# LevelConverter.net
KiCad netlist of a schematic drawn in Altium Designer
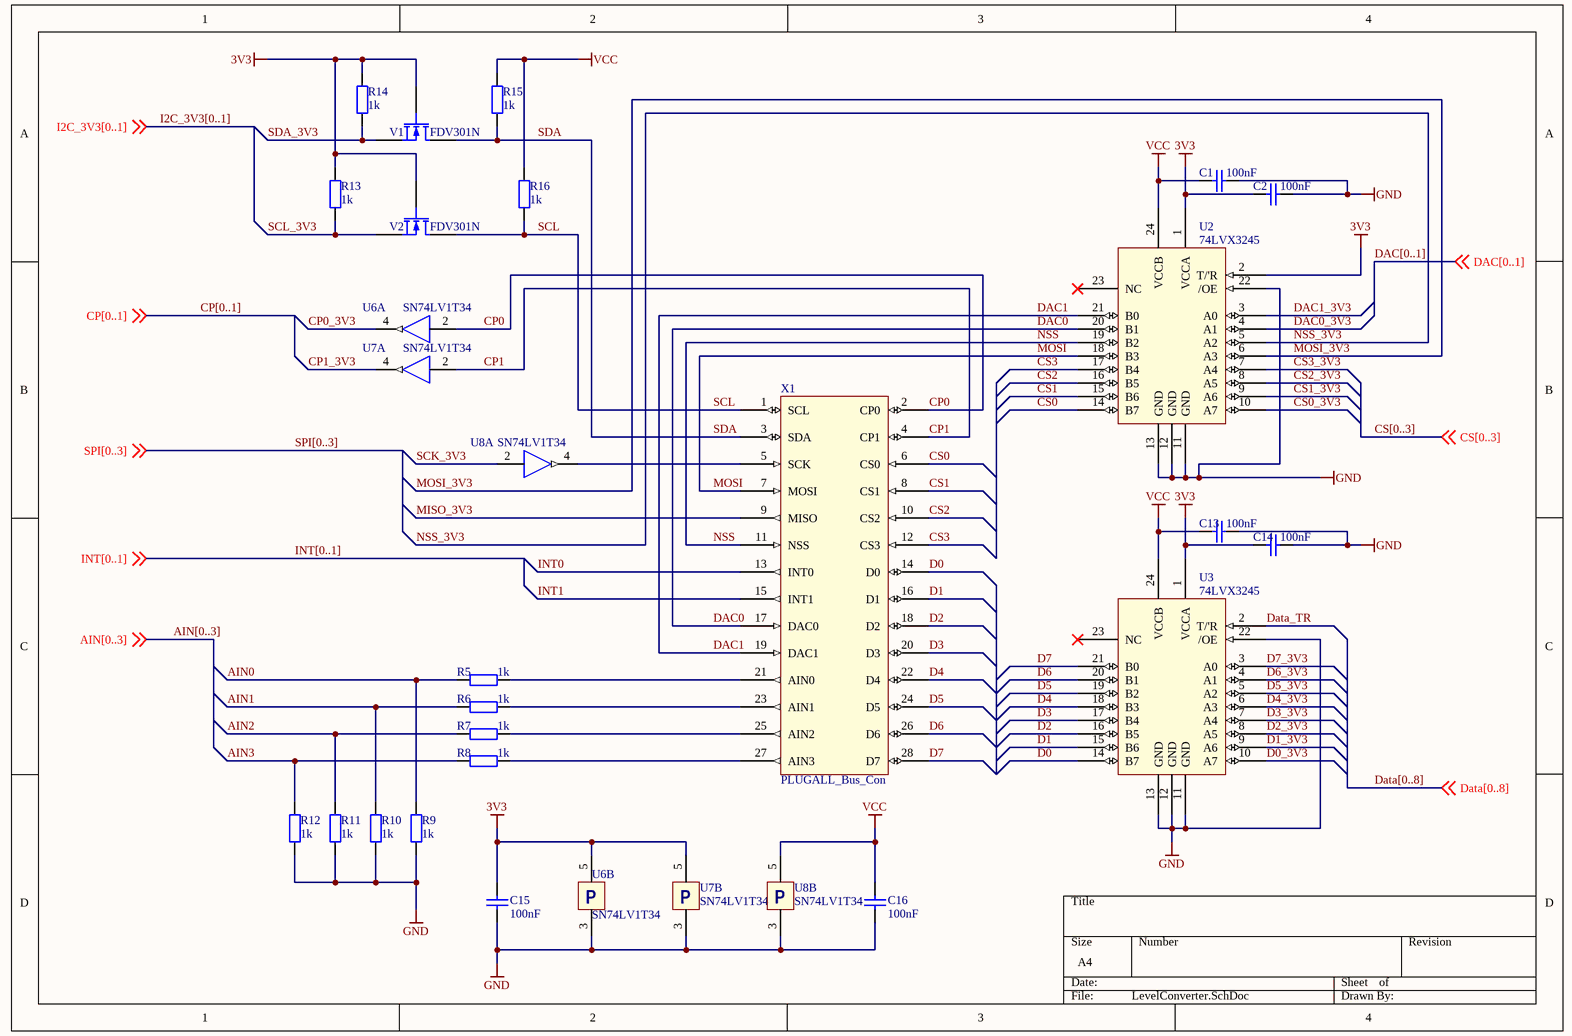
[diagram p0: LevelConverter.SchDoc]

(export (version "E")
  (design (tool "Eeschema 10.0.6"))
  (components
    (comp (ref "C1")
      (value "100nF")
      (footprint "0805")
      (fields (field (name "Comment") "C"))
      (libsource (lib "Schlib1") (part "C"))
    )
    (comp (ref "C2")
      (value "100nF")
      (footprint "0805")
      (fields (field (name "Comment") "C"))
      (libsource (lib "Schlib1") (part "C"))
    )
    (comp (ref "C13")
      (value "100nF")
      (footprint "0805")
      (fields (field (name "Comment") "C"))
      (libsource (lib "Schlib1") (part "C"))
    )
    (comp (ref "C14")
      (value "100nF")
      (footprint "0805")
      (fields (field (name "Comment") "C"))
      (libsource (lib "Schlib1") (part "C"))
    )
    (comp (ref "C15")
      (value "100nF")
      (footprint "0805")
      (fields (field (name "Comment") "C"))
      (libsource (lib "Schlib1") (part "C"))
    )
    (comp (ref "C16")
      (value "100nF")
      (footprint "0805")
      (fields (field (name "Comment") "C"))
      (libsource (lib "Schlib1") (part "C"))
    )
    (comp (ref "R5")
      (value "1k")
      (footprint "R_0603")
      (fields (field (name "Comment") "R"))
      (libsource (lib "") (part "RES_EU_1"))
    )
    (comp (ref "R6")
      (value "1k")
      (footprint "R_0603")
      (fields (field (name "Comment") "R"))
      (libsource (lib "") (part "RES_EU_1"))
    )
    (comp (ref "R7")
      (value "1k")
      (footprint "R_0603")
      (fields (field (name "Comment") "R"))
      (libsource (lib "") (part "RES_EU_1"))
    )
    (comp (ref "R8")
      (value "1k")
      (footprint "R_0603")
      (fields (field (name "Comment") "R"))
      (libsource (lib "") (part "RES_EU_1"))
    )
    (comp (ref "R9")
      (value "1k")
      (footprint "R_0603")
      (fields (field (name "Comment") "R"))
      (libsource (lib "Schlib1") (part "RES_EU"))
    )
    (comp (ref "R10")
      (value "1k")
      (footprint "R_0603")
      (fields (field (name "Comment") "R"))
      (libsource (lib "Schlib1") (part "RES_EU"))
    )
    (comp (ref "R11")
      (value "1k")
      (footprint "R_0603")
      (fields (field (name "Comment") "R"))
      (libsource (lib "Schlib1") (part "RES_EU"))
    )
    (comp (ref "R12")
      (value "1k")
      (footprint "R_0603")
      (fields (field (name "Comment") "R"))
      (libsource (lib "Schlib1") (part "RES_EU"))
    )
    (comp (ref "R13")
      (value "1k")
      (footprint "R_0603")
      (fields (field (name "Comment") "R"))
      (libsource (lib "Schlib1") (part "RES_EU"))
    )
    (comp (ref "R14")
      (value "1k")
      (footprint "R_0603")
      (fields (field (name "Comment") "R"))
      (libsource (lib "Schlib1") (part "RES_EU"))
    )
    (comp (ref "R15")
      (value "1k")
      (footprint "R_0603")
      (fields (field (name "Comment") "R"))
      (libsource (lib "Schlib1") (part "RES_EU"))
    )
    (comp (ref "R16")
      (value "1k")
      (footprint "R_0603")
      (fields (field (name "Comment") "R"))
      (libsource (lib "Schlib1") (part "RES_EU"))
    )
    (comp (ref "U2") (value "74LVX3245") (footprint "TSSOP24") (libsource (lib "Schlib1") (part "74LVX3245")))
    (comp (ref "U3") (value "74LVX3245") (footprint "TSSOP24") (libsource (lib "Schlib1") (part "74LVX3245")))
    (comp (ref "U6") (value "SN74LV1T34") (footprint "DCK") (libsource (lib "Schlib1") (part "SN74LV1T34")))
    (comp (ref "U7") (value "SN74LV1T34") (footprint "DCK") (libsource (lib "") (part "SN74LV1T34_1")))
    (comp (ref "U8") (value "SN74LV1T34") (footprint "DCK") (libsource (lib "Schlib1") (part "SN74LV1T34")))
    (comp (ref "V1") (value "FDV301N") (footprint "SOT-23") (libsource (lib "Schlib1") (part "MOSFET-N")))
    (comp (ref "V2") (value "FDV301N") (footprint "SOT-23") (libsource (lib "Schlib1") (part "MOSFET-N")))
    (comp (ref "X1")
      (value "PLUGALL_Bus_Con")
      (footprint "CON14X2")
      (description "PLUGALL Card Connector")
      (libsource (lib "Schlib1") (part "PLUGALL_Bus_Con"))
    )
  )
  (nets
    (net (code "1") (name "/CP0_3V3") (class "Default")
      (node (ref "U6") (pin "4") (pinfunction "OUT_4") (pintype "output"))
    )
    (net (code "2") (name "/CP1_3V3") (class "Default")
      (node (ref "U7") (pin "4") (pinfunction "OUT_4") (pintype "output"))
    )
    (net (code "3") (name "/CS0_3V3") (class "Default")
      (node (ref "U2") (pin "10") (pinfunction "A7_10") (pintype "bidirectional"))
    )
    (net (code "4") (name "/CS1_3V3") (class "Default")
      (node (ref "U2") (pin "9") (pinfunction "A6_9") (pintype "bidirectional"))
    )
    (net (code "5") (name "/CS2_3V3") (class "Default")
      (node (ref "U2") (pin "8") (pinfunction "A5_8") (pintype "bidirectional"))
    )
    (net (code "6") (name "/CS3_3V3") (class "Default")
      (node (ref "U2") (pin "7") (pinfunction "A4_7") (pintype "bidirectional"))
    )
    (net (code "7") (name "/D0") (class "Default")
      (node (ref "U3") (pin "14") (pinfunction "B7_14") (pintype "bidirectional"))
      (node (ref "X1") (pin "14") (pinfunction "D0_14") (pintype "bidirectional"))
    )
    (net (code "8") (name "/D0_3V3") (class "Default")
      (node (ref "U3") (pin "10") (pinfunction "A7_10") (pintype "bidirectional"))
    )
    (net (code "9") (name "/D1") (class "Default")
      (node (ref "U3") (pin "15") (pinfunction "B6_15") (pintype "bidirectional"))
      (node (ref "X1") (pin "16") (pinfunction "D1_16") (pintype "bidirectional"))
    )
    (net (code "10") (name "/D1_3V3") (class "Default")
      (node (ref "U3") (pin "9") (pinfunction "A6_9") (pintype "bidirectional"))
    )
    (net (code "11") (name "/D2") (class "Default")
      (node (ref "U3") (pin "16") (pinfunction "B5_16") (pintype "bidirectional"))
      (node (ref "X1") (pin "18") (pinfunction "D2_18") (pintype "bidirectional"))
    )
    (net (code "12") (name "/D2_3V3") (class "Default")
      (node (ref "U3") (pin "8") (pinfunction "A5_8") (pintype "bidirectional"))
    )
    (net (code "13") (name "/D3") (class "Default")
      (node (ref "U3") (pin "17") (pinfunction "B4_17") (pintype "bidirectional"))
      (node (ref "X1") (pin "20") (pinfunction "D3_20") (pintype "bidirectional"))
    )
    (net (code "14") (name "/D3_3V3") (class "Default")
      (node (ref "U3") (pin "7") (pinfunction "A4_7") (pintype "bidirectional"))
    )
    (net (code "15") (name "/D4") (class "Default")
      (node (ref "U3") (pin "18") (pinfunction "B3_18") (pintype "bidirectional"))
      (node (ref "X1") (pin "22") (pinfunction "D4_22") (pintype "bidirectional"))
    )
    (net (code "16") (name "/D4_3V3") (class "Default")
      (node (ref "U3") (pin "6") (pinfunction "A3_6") (pintype "bidirectional"))
    )
    (net (code "17") (name "/D5") (class "Default")
      (node (ref "U3") (pin "19") (pinfunction "B2_19") (pintype "bidirectional"))
      (node (ref "X1") (pin "24") (pinfunction "D5_24") (pintype "bidirectional"))
    )
    (net (code "18") (name "/D5_3V3") (class "Default")
      (node (ref "U3") (pin "5") (pinfunction "A2_5") (pintype "bidirectional"))
    )
    (net (code "19") (name "/D6") (class "Default")
      (node (ref "U3") (pin "20") (pinfunction "B1_20") (pintype "bidirectional"))
      (node (ref "X1") (pin "26") (pinfunction "D6_26") (pintype "bidirectional"))
    )
    (net (code "20") (name "/D6_3V3") (class "Default")
      (node (ref "U3") (pin "4") (pinfunction "A1_4") (pintype "bidirectional"))
    )
    (net (code "21") (name "/D7") (class "Default")
      (node (ref "U3") (pin "21") (pinfunction "B0_21") (pintype "bidirectional"))
      (node (ref "X1") (pin "28") (pinfunction "D7_28") (pintype "bidirectional"))
    )
    (net (code "22") (name "/D7_3V3") (class "Default")
      (node (ref "U3") (pin "3") (pinfunction "A0_3") (pintype "bidirectional"))
    )
    (net (code "23") (name "/DAC0_3V3") (class "Default")
      (node (ref "U2") (pin "4") (pinfunction "A1_4") (pintype "bidirectional"))
    )
    (net (code "24") (name "/DAC1_3V3") (class "Default")
      (node (ref "U2") (pin "3") (pinfunction "A0_3") (pintype "bidirectional"))
    )
    (net (code "25") (name "/Data_TR") (class "Default")
      (node (ref "U3") (pin "2") (pinfunction "T/'R_2") (pintype "input"))
    )
    (net (code "26") (name "/MISO_3V3") (class "Default")
      (node (ref "X1") (pin "9") (pinfunction "MISO_9") (pintype "output"))
    )
    (net (code "27") (name "/MOSI") (class "Default")
      (node (ref "U2") (pin "18") (pinfunction "B3_18") (pintype "bidirectional"))
      (node (ref "X1") (pin "7") (pinfunction "MOSI_7") (pintype "input"))
    )
    (net (code "28") (name "/MOSI_3V3") (class "Default")
      (node (ref "U2") (pin "6") (pinfunction "A3_6") (pintype "bidirectional"))
    )
    (net (code "29") (name "/NSS") (class "Default")
      (node (ref "U2") (pin "19") (pinfunction "B2_19") (pintype "bidirectional"))
      (node (ref "X1") (pin "11") (pinfunction "NSS_11") (pintype "input"))
    )
    (net (code "30") (name "/NSS_3V3") (class "Default")
      (node (ref "U2") (pin "5") (pinfunction "A2_5") (pintype "bidirectional"))
    )
    (net (code "31") (name "/SCK_3V3") (class "Default")
      (node (ref "U8") (pin "2") (pinfunction "IN_2") (pintype "passive"))
    )
    (net (code "32") (name "/SCL") (class "Default")
      (node (ref "R16") (pin "1") (pinfunction "1_1") (pintype "passive"))
      (node (ref "V2") (pin "1") (pinfunction "D_1") (pintype "passive"))
      (node (ref "X1") (pin "1") (pinfunction "SCL_1") (pintype "bidirectional"))
    )
    (net (code "33") (name "/SCL_3V3") (class "Default")
      (node (ref "R13") (pin "1") (pinfunction "1_1") (pintype "passive"))
      (node (ref "V2") (pin "3") (pinfunction "S_3") (pintype "passive"))
    )
    (net (code "34") (name "/SDA") (class "Default")
      (node (ref "R15") (pin "1") (pinfunction "1_1") (pintype "passive"))
      (node (ref "V1") (pin "1") (pinfunction "D_1") (pintype "passive"))
      (node (ref "X1") (pin "3") (pinfunction "SDA_3") (pintype "bidirectional"))
    )
    (net (code "35") (name "/SDA_3V3") (class "Default")
      (node (ref "R14") (pin "1") (pinfunction "1_1") (pintype "passive"))
      (node (ref "V1") (pin "3") (pinfunction "S_3") (pintype "passive"))
    )
    (net (code "36") (name "3V3") (class "Default")
      (node (ref "C14") (pin "1") (pinfunction "1_1") (pintype "passive"))
      (node (ref "C15") (pin "2") (pinfunction "2_2") (pintype "passive"))
      (node (ref "C2") (pin "1") (pinfunction "1_1") (pintype "passive"))
      (node (ref "R13") (pin "2") (pinfunction "2_2") (pintype "passive"))
      (node (ref "R14") (pin "2") (pinfunction "2_2") (pintype "passive"))
      (node (ref "U2") (pin "1") (pinfunction "VCCA_1") (pintype "power_in"))
      (node (ref "U2") (pin "2") (pinfunction "T/'R_2") (pintype "input"))
      (node (ref "U3") (pin "1") (pinfunction "VCCA_1") (pintype "power_in"))
      (node (ref "U6") (pin "5") (pinfunction "VCC_5") (pintype "power_in"))
      (node (ref "U7") (pin "5") (pinfunction "VCC_5") (pintype "power_in"))
      (node (ref "V1") (pin "2") (pinfunction "G_2") (pintype "passive"))
      (node (ref "V2") (pin "2") (pinfunction "G_2") (pintype "passive"))
    )
    (net (code "37") (name "AIN0") (class "Default")
      (node (ref "R5") (pin "1") (pinfunction "1_1") (pintype "passive"))
      (node (ref "R9") (pin "2") (pinfunction "2_2") (pintype "passive"))
    )
    (net (code "38") (name "AIN1") (class "Default")
      (node (ref "R10") (pin "2") (pinfunction "2_2") (pintype "passive"))
      (node (ref "R6") (pin "1") (pinfunction "1_1") (pintype "passive"))
    )
    (net (code "39") (name "AIN2") (class "Default")
      (node (ref "R11") (pin "2") (pinfunction "2_2") (pintype "passive"))
      (node (ref "R7") (pin "1") (pinfunction "1_1") (pintype "passive"))
    )
    (net (code "40") (name "AIN3") (class "Default")
      (node (ref "R12") (pin "2") (pinfunction "2_2") (pintype "passive"))
      (node (ref "R8") (pin "1") (pinfunction "1_1") (pintype "passive"))
    )
    (net (code "42") (name "CP0") (class "Default")
      (node (ref "U6") (pin "2") (pinfunction "IN_2") (pintype "passive"))
      (node (ref "X1") (pin "2") (pinfunction "CP0_2") (pintype "bidirectional"))
    )
    (net (code "43") (name "CP1") (class "Default")
      (node (ref "U7") (pin "2") (pinfunction "IN_2") (pintype "passive"))
      (node (ref "X1") (pin "4") (pinfunction "CP1_4") (pintype "bidirectional"))
    )
    (net (code "45") (name "CS0") (class "Default")
      (node (ref "U2") (pin "14") (pinfunction "B7_14") (pintype "bidirectional"))
      (node (ref "X1") (pin "6") (pinfunction "CS0_6") (pintype "input"))
    )
    (net (code "46") (name "CS1") (class "Default")
      (node (ref "U2") (pin "15") (pinfunction "B6_15") (pintype "bidirectional"))
      (node (ref "X1") (pin "8") (pinfunction "CS1_8") (pintype "input"))
    )
    (net (code "47") (name "CS2") (class "Default")
      (node (ref "U2") (pin "16") (pinfunction "B5_16") (pintype "bidirectional"))
      (node (ref "X1") (pin "10") (pinfunction "CS2_10") (pintype "input"))
    )
    (net (code "48") (name "CS3") (class "Default")
      (node (ref "U2") (pin "17") (pinfunction "B4_17") (pintype "bidirectional"))
      (node (ref "X1") (pin "12") (pinfunction "CS3_12") (pintype "input"))
    )
    (net (code "50") (name "DAC0") (class "Default")
      (node (ref "U2") (pin "20") (pinfunction "B1_20") (pintype "bidirectional"))
      (node (ref "X1") (pin "17") (pinfunction "DAC0_17") (pintype "input"))
    )
    (net (code "51") (name "DAC1") (class "Default")
      (node (ref "U2") (pin "21") (pinfunction "B0_21") (pintype "bidirectional"))
      (node (ref "X1") (pin "19") (pinfunction "DAC1_19") (pintype "input"))
    )
    (net (code "54") (name "GND") (class "Default")
      (node (ref "C1") (pin "2") (pinfunction "2_2") (pintype "passive"))
      (node (ref "C13") (pin "2") (pinfunction "2_2") (pintype "passive"))
      (node (ref "C14") (pin "2") (pinfunction "2_2") (pintype "passive"))
      (node (ref "C15") (pin "1") (pinfunction "1_1") (pintype "passive"))
      (node (ref "C16") (pin "1") (pinfunction "1_1") (pintype "passive"))
      (node (ref "C2") (pin "2") (pinfunction "2_2") (pintype "passive"))
      (node (ref "R10") (pin "1") (pinfunction "1_1") (pintype "passive"))
      (node (ref "R11") (pin "1") (pinfunction "1_1") (pintype "passive"))
      (node (ref "R12") (pin "1") (pinfunction "1_1") (pintype "passive"))
      (node (ref "R9") (pin "1") (pinfunction "1_1") (pintype "passive"))
      (node (ref "U2") (pin "11") (pinfunction "GND_11") (pintype "power_in"))
      (node (ref "U2") (pin "12") (pinfunction "GND_12") (pintype "power_in"))
      (node (ref "U2") (pin "13") (pinfunction "GND_13") (pintype "power_in"))
      (node (ref "U2") (pin "22") (pinfunction "/OE_22") (pintype "input"))
      (node (ref "U3") (pin "11") (pinfunction "GND_11") (pintype "power_in"))
      (node (ref "U3") (pin "12") (pinfunction "GND_12") (pintype "power_in"))
      (node (ref "U3") (pin "13") (pinfunction "GND_13") (pintype "power_in"))
      (node (ref "U3") (pin "22") (pinfunction "/OE_22") (pintype "input"))
      (node (ref "U6") (pin "3") (pinfunction "GND_3") (pintype "power_in"))
      (node (ref "U7") (pin "3") (pinfunction "GND_3") (pintype "power_in"))
      (node (ref "U8") (pin "3") (pinfunction "GND_3") (pintype "power_in"))
    )
    (net (code "56") (name "INT0") (class "Default")
      (node (ref "X1") (pin "13") (pinfunction "INT0_13") (pintype "output"))
    )
    (net (code "57") (name "INT1") (class "Default")
      (node (ref "X1") (pin "15") (pinfunction "INT1_15") (pintype "output"))
    )
    (net (code "59") (name "Net-(U8A-OUT)") (class "Default")
      (node (ref "U8") (pin "4") (pinfunction "OUT_4") (pintype "output"))
      (node (ref "X1") (pin "5") (pinfunction "SCK_5") (pintype "input"))
    )
    (net (code "60") (name "Net-(X1-AIN0)") (class "Default")
      (node (ref "R5") (pin "2") (pinfunction "2_2") (pintype "passive"))
      (node (ref "X1") (pin "21") (pinfunction "AIN0_21") (pintype "output"))
    )
    (net (code "61") (name "Net-(X1-AIN1)") (class "Default")
      (node (ref "R6") (pin "2") (pinfunction "2_2") (pintype "passive"))
      (node (ref "X1") (pin "23") (pinfunction "AIN1_23") (pintype "output"))
    )
    (net (code "62") (name "Net-(X1-AIN2)") (class "Default")
      (node (ref "R7") (pin "2") (pinfunction "2_2") (pintype "passive"))
      (node (ref "X1") (pin "25") (pinfunction "AIN2_25") (pintype "output"))
    )
    (net (code "63") (name "Net-(X1-AIN3)") (class "Default")
      (node (ref "R8") (pin "2") (pinfunction "2_2") (pintype "passive"))
      (node (ref "X1") (pin "27") (pinfunction "AIN3_27") (pintype "output"))
    )
    (net (code "65") (name "VCC") (class "Default")
      (node (ref "C1") (pin "1") (pinfunction "1_1") (pintype "passive"))
      (node (ref "C13") (pin "1") (pinfunction "1_1") (pintype "passive"))
      (node (ref "C16") (pin "2") (pinfunction "2_2") (pintype "passive"))
      (node (ref "R15") (pin "2") (pinfunction "2_2") (pintype "passive"))
      (node (ref "R16") (pin "2") (pinfunction "2_2") (pintype "passive"))
      (node (ref "U2") (pin "24") (pinfunction "VCCB_24") (pintype "power_in"))
      (node (ref "U3") (pin "24") (pinfunction "VCCB_24") (pintype "power_in"))
      (node (ref "U8") (pin "5") (pinfunction "VCC_5") (pintype "power_in"))
    )
    (net (code "66") (name "unconnected-(U2-NC-Pad23)") (class "Default")
      (node (ref "U2") (pin "23") (pinfunction "NC_23") (pintype "passive+no_connect"))
    )
    (net (code "67") (name "unconnected-(U3-NC-Pad23)") (class "Default")
      (node (ref "U3") (pin "23") (pinfunction "NC_23") (pintype "passive+no_connect"))
    )
  )
)
